# mkstepper23.net
KiCad netlist of a schematic drawn in EAGLE
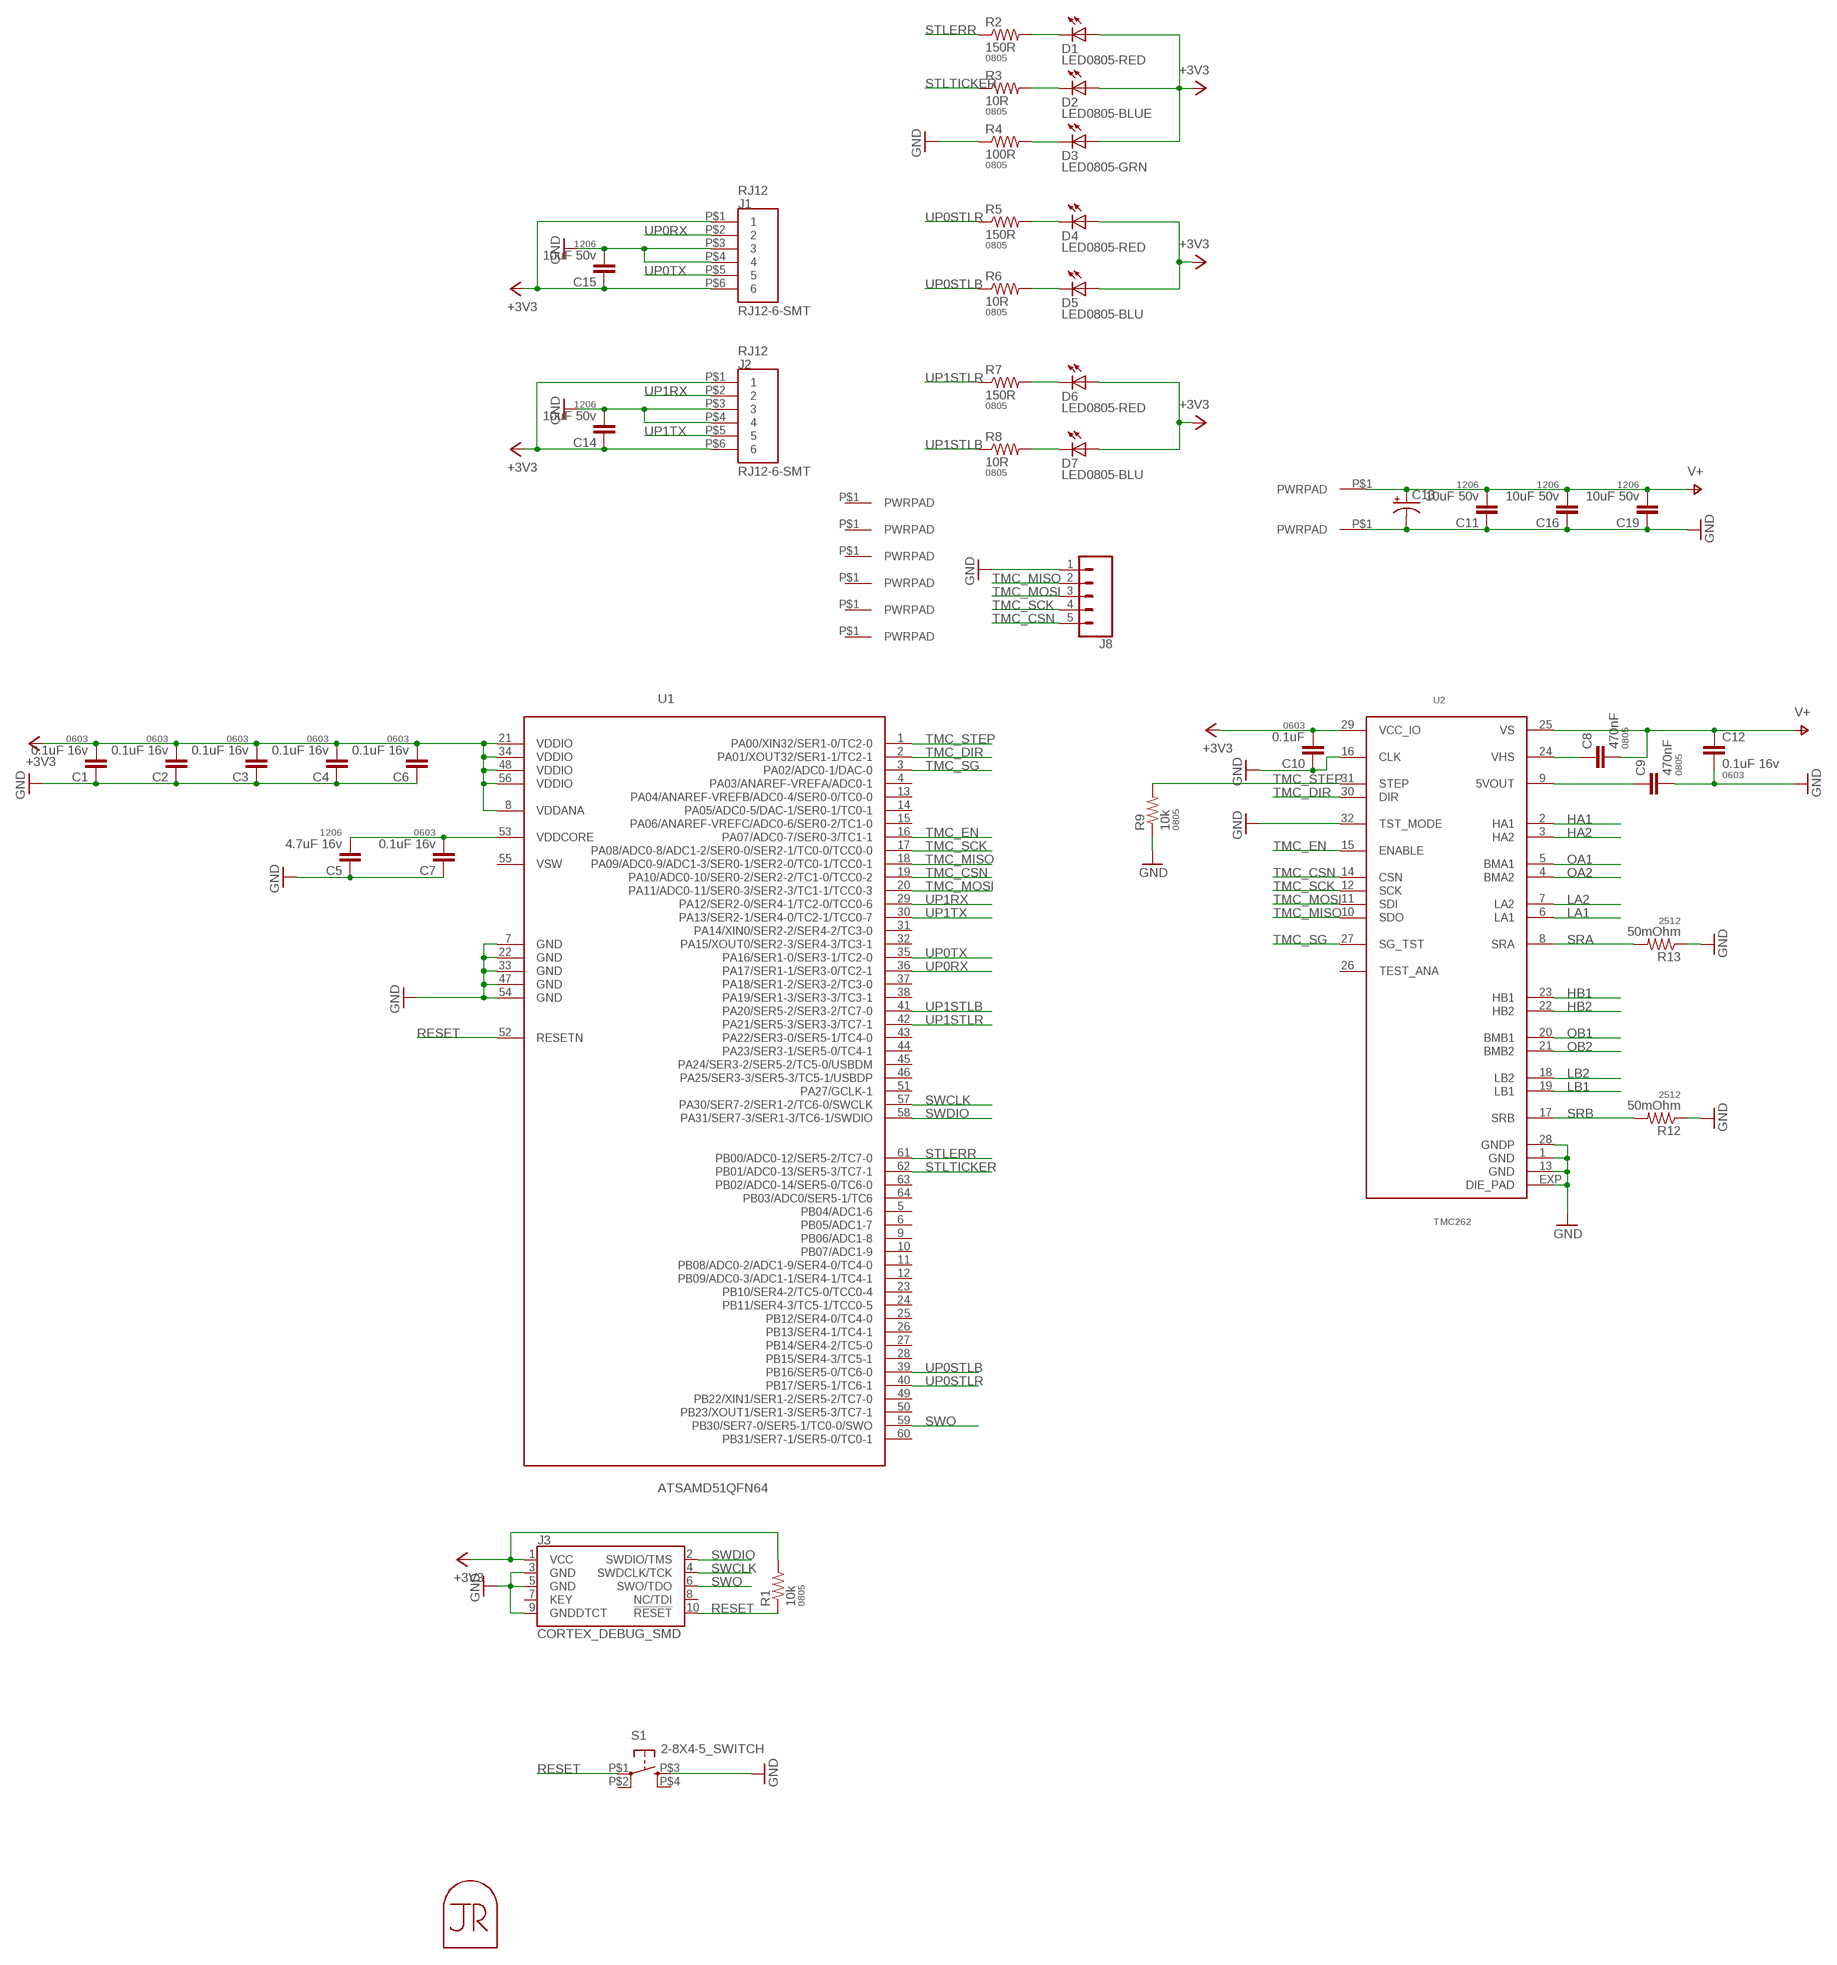
[diagram p0: schematic, sheet 1, part 1 of 2]
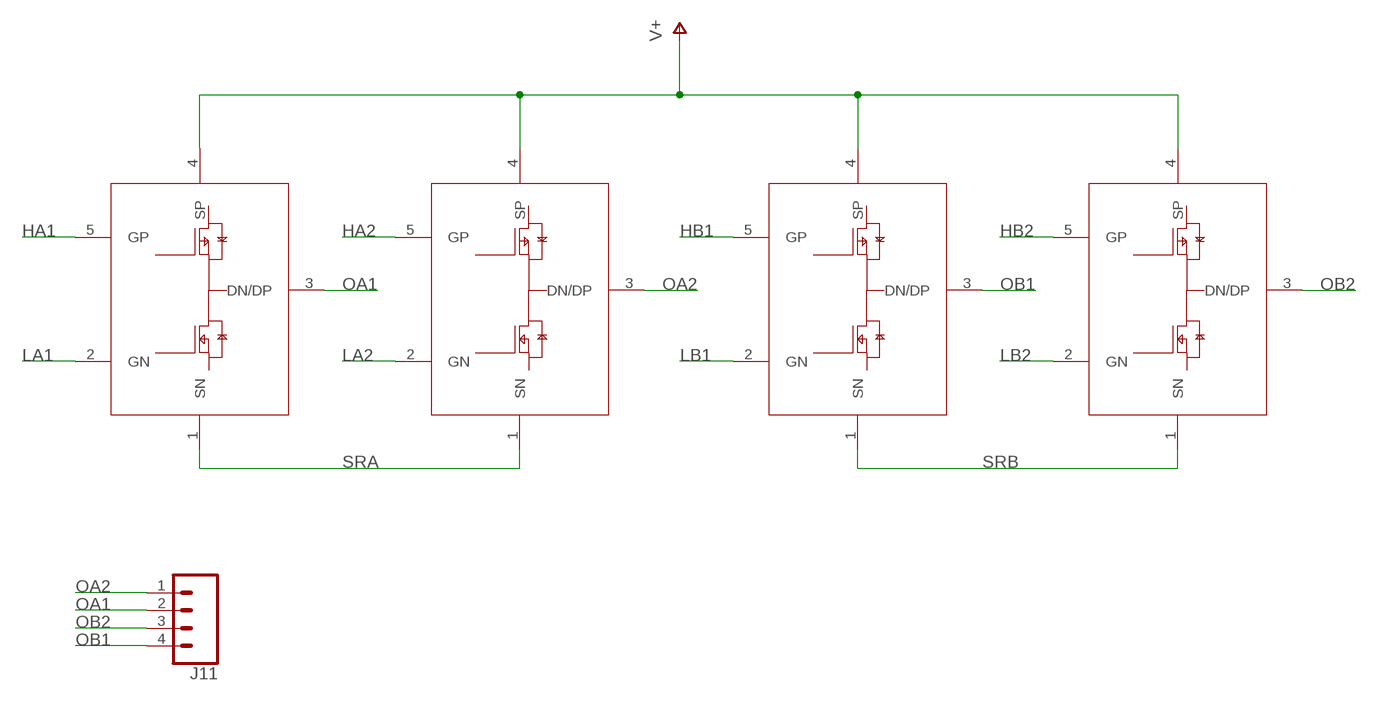
[diagram p1: schematic, sheet 1, part 2 of 2]

(export (version "E")
  (design (tool "Eeschema 10.0.6"))
  (components
    (comp (ref "C1")
      (value "0.1uF 16v")
      (footprint "eagle-import:0603-CAP")
      (libsource (lib "eagle-import") (part "CAP0603-CAP"))
    )
    (comp (ref "C2")
      (value "0.1uF 16v")
      (footprint "eagle-import:0603-CAP")
      (libsource (lib "eagle-import") (part "CAP0603-CAP"))
    )
    (comp (ref "C3")
      (value "0.1uF 16v")
      (footprint "eagle-import:0603-CAP")
      (libsource (lib "eagle-import") (part "CAP0603-CAP"))
    )
    (comp (ref "C4")
      (value "0.1uF 16v")
      (footprint "eagle-import:0603-CAP")
      (libsource (lib "eagle-import") (part "CAP0603-CAP"))
    )
    (comp (ref "C5")
      (value "4.7uF 16v")
      (footprint "eagle-import:1206")
      (libsource (lib "eagle-import") (part "CAP1206"))
    )
    (comp (ref "C6")
      (value "0.1uF 16v")
      (footprint "eagle-import:0603-CAP")
      (libsource (lib "eagle-import") (part "CAP0603-CAP"))
    )
    (comp (ref "C7")
      (value "0.1uF 16v")
      (footprint "eagle-import:0603-CAP")
      (libsource (lib "eagle-import") (part "CAP0603-CAP"))
    )
    (comp (ref "C8")
      (value "470nF")
      (footprint "eagle-import:0805")
      (libsource (lib "eagle-import") (part "CAP0805"))
    )
    (comp (ref "C9")
      (value "470nF")
      (footprint "eagle-import:0805")
      (libsource (lib "eagle-import") (part "CAP0805"))
    )
    (comp (ref "C10")
      (value "0.1uF")
      (footprint "eagle-import:0603-CAP")
      (libsource (lib "eagle-import") (part "CAP0603-CAP"))
    )
    (comp (ref "C11")
      (value "10uF 50v")
      (footprint "eagle-import:1206")
      (libsource (lib "eagle-import") (part "CAP1206"))
    )
    (comp (ref "C12")
      (value "0.1uF 16v")
      (footprint "eagle-import:0603-CAP")
      (libsource (lib "eagle-import") (part "CAP0603-CAP"))
    )
    (comp (ref "C13")
      (value "CAP-POL-6.6X6.6")
      (footprint "eagle-import:6.6X6.6-CAP")
      (libsource (lib "eagle-import") (part "CAP-POL-6.6X6.6"))
    )
    (comp (ref "C14")
      (value "10uF 50v")
      (footprint "eagle-import:1206")
      (libsource (lib "eagle-import") (part "CAP1206"))
    )
    (comp (ref "C15")
      (value "10uF 50v")
      (footprint "eagle-import:1206")
      (libsource (lib "eagle-import") (part "CAP1206"))
    )
    (comp (ref "C16")
      (value "10uF 50v")
      (footprint "eagle-import:1206")
      (libsource (lib "eagle-import") (part "CAP1206"))
    )
    (comp (ref "C19")
      (value "10uF 50v")
      (footprint "eagle-import:1206")
      (libsource (lib "eagle-import") (part "CAP1206"))
    )
    (comp (ref "D1")
      (value "LED0805-RED")
      (footprint "eagle-import:LED0805")
      (libsource (lib "eagle-import") (part "LED0805"))
    )
    (comp (ref "D2")
      (value "LED0805-BLUE")
      (footprint "eagle-import:LED0805")
      (libsource (lib "eagle-import") (part "LED0805"))
    )
    (comp (ref "D3")
      (value "LED0805-GRN")
      (footprint "eagle-import:LED0805")
      (libsource (lib "eagle-import") (part "LED0805"))
    )
    (comp (ref "D4")
      (value "LED0805-RED")
      (footprint "eagle-import:LED0805")
      (libsource (lib "eagle-import") (part "LED0805"))
    )
    (comp (ref "D5")
      (value "LED0805-BLU")
      (footprint "eagle-import:LED0805")
      (libsource (lib "eagle-import") (part "LED0805"))
    )
    (comp (ref "D6")
      (value "LED0805-RED")
      (footprint "eagle-import:LED0805")
      (libsource (lib "eagle-import") (part "LED0805"))
    )
    (comp (ref "D7")
      (value "LED0805-BLU")
      (footprint "eagle-import:LED0805")
      (libsource (lib "eagle-import") (part "LED0805"))
    )
    (comp (ref "J1")
      (value "RJ12-6-SMT")
      (footprint "eagle-import:RJ12-6-SMT")
      (libsource (lib "eagle-import") (part "RJ12-6-SMT"))
    )
    (comp (ref "J2")
      (value "RJ12-6-SMT")
      (footprint "eagle-import:RJ12-6-SMT")
      (libsource (lib "eagle-import") (part "RJ12-6-SMT"))
    )
    (comp (ref "J3")
      (value "CORTEX_DEBUG_SMD")
      (footprint "eagle-import:SAMTECH_FTSH-105-01")
      (libsource (lib "eagle-import") (part "CORTEX_DEBUG_SMD"))
    )
    (comp (ref "J4")
      (value "PWRPADM3-SKINNY")
      (footprint "eagle-import:PWRPAD_3-25MM-SKINNY")
      (libsource (lib "eagle-import") (part "PWRPADM3-SKINNY"))
    )
    (comp (ref "J5")
      (value "PWRPADM3-SKINNY")
      (footprint "eagle-import:PWRPAD_3-25MM-SKINNY")
      (libsource (lib "eagle-import") (part "PWRPADM3-SKINNY"))
    )
    (comp (ref "J6")
      (value "PWRPADM3-SKINNY")
      (footprint "eagle-import:PWRPAD_3-25MM-SKINNY")
      (libsource (lib "eagle-import") (part "PWRPADM3-SKINNY"))
    )
    (comp (ref "J7")
      (value "PWRPADM3-SKINNY")
      (footprint "eagle-import:PWRPAD_3-25MM-SKINNY")
      (libsource (lib "eagle-import") (part "PWRPADM3-SKINNY"))
    )
    (comp (ref "J8")
      (value "CONN_05NO_SILK")
      (footprint "eagle-import:1X05_NO_SILK")
      (libsource (lib "eagle-import") (part "CONN_05NO_SILK"))
    )
    (comp (ref "J9")
      (value "PWRPAD")
      (footprint "eagle-import:PWRPAD_M3-PEM-MOUNT")
      (libsource (lib "eagle-import") (part "PWRPAD"))
    )
    (comp (ref "J10")
      (value "PWRPAD")
      (footprint "eagle-import:PWRPAD_M3-PEM-MOUNT")
      (libsource (lib "eagle-import") (part "PWRPAD"))
    )
    (comp (ref "J11")
      (value "CONN_04LONGPADS")
      (footprint "eagle-import:1X04_LONGPADS")
      (libsource (lib "eagle-import") (part "CONN_04LONGPADS"))
    )
    (comp (ref "J12")
      (value "PWRPADM3-SKINNY")
      (footprint "eagle-import:PWRPAD_3-25MM-SKINNY")
      (libsource (lib "eagle-import") (part "PWRPADM3-SKINNY"))
    )
    (comp (ref "J13")
      (value "PWRPADM3-SKINNY")
      (footprint "eagle-import:PWRPAD_3-25MM-SKINNY")
      (libsource (lib "eagle-import") (part "PWRPADM3-SKINNY"))
    )
    (comp (ref "MP1")
      (value "JRTOMBSTONE")
      (footprint "eagle-import:JRTOMBSTONE")
      (libsource (lib "eagle-import") (part "JRTOMBSTONE"))
    )
    (comp (ref "Q1")
      (value "PNPAIR-FDD8424H")
      (footprint "eagle-import:DPAK-5")
      (libsource (lib "eagle-import") (part "PNPAIR-FDD8424H"))
    )
    (comp (ref "Q2")
      (value "PNPAIR-FDD8424H")
      (footprint "eagle-import:DPAK-5")
      (libsource (lib "eagle-import") (part "PNPAIR-FDD8424H"))
    )
    (comp (ref "Q3")
      (value "PNPAIR-FDD8424H")
      (footprint "eagle-import:DPAK-5")
      (libsource (lib "eagle-import") (part "PNPAIR-FDD8424H"))
    )
    (comp (ref "Q4")
      (value "PNPAIR-FDD8424H")
      (footprint "eagle-import:DPAK-5")
      (libsource (lib "eagle-import") (part "PNPAIR-FDD8424H"))
    )
    (comp (ref "R1")
      (value "10k")
      (footprint "eagle-import:0805")
      (libsource (lib "eagle-import") (part "RESISTOR0805-RES"))
    )
    (comp (ref "R2")
      (value "150R")
      (footprint "eagle-import:0805")
      (libsource (lib "eagle-import") (part "RESISTOR0805-RES"))
    )
    (comp (ref "R3")
      (value "10R")
      (footprint "eagle-import:0805")
      (libsource (lib "eagle-import") (part "RESISTOR0805-RES"))
    )
    (comp (ref "R4")
      (value "100R")
      (footprint "eagle-import:0805")
      (libsource (lib "eagle-import") (part "RESISTOR0805-RES"))
    )
    (comp (ref "R5")
      (value "150R")
      (footprint "eagle-import:0805")
      (libsource (lib "eagle-import") (part "RESISTOR0805-RES"))
    )
    (comp (ref "R6")
      (value "10R")
      (footprint "eagle-import:0805")
      (libsource (lib "eagle-import") (part "RESISTOR0805-RES"))
    )
    (comp (ref "R7")
      (value "150R")
      (footprint "eagle-import:0805")
      (libsource (lib "eagle-import") (part "RESISTOR0805-RES"))
    )
    (comp (ref "R8")
      (value "10R")
      (footprint "eagle-import:0805")
      (libsource (lib "eagle-import") (part "RESISTOR0805-RES"))
    )
    (comp (ref "R9")
      (value "10k")
      (footprint "eagle-import:0805")
      (libsource (lib "eagle-import") (part "RESISTOR0805-RES"))
    )
    (comp (ref "R12")
      (value "50mOhm")
      (footprint "eagle-import:R2512")
      (libsource (lib "eagle-import") (part "RESISTOR2512"))
    )
    (comp (ref "R13")
      (value "50mOhm")
      (footprint "eagle-import:R2512")
      (libsource (lib "eagle-import") (part "RESISTOR2512"))
    )
    (comp (ref "S1")
      (value "2-8X4-5_SWITCH")
      (footprint "eagle-import:TACT-SWITCH-KMR6")
      (libsource (lib "eagle-import") (part "2-8X4-5_SWITCH"))
    )
    (comp (ref "U1")
      (value "ATSAMD51QFN64")
      (footprint "eagle-import:QFN-64-9X9MM")
      (libsource (lib "eagle-import") (part "ATSAMD51QFN64"))
    )
    (comp (ref "U2")
      (value "TMC262")
      (footprint "eagle-import:QFN32")
      (libsource (lib "eagle-import") (part "TMC262"))
    )
  )
  (nets
    (net (code "1") (name "+3V3") (class "Default")
      (node (ref "C1") (pin "2") (pinfunction "2_2") (pintype "passive"))
      (node (ref "C10") (pin "2") (pinfunction "2_2") (pintype "passive"))
      (node (ref "C14") (pin "1") (pinfunction "1_1") (pintype "passive"))
      (node (ref "C15") (pin "1") (pinfunction "1_1") (pintype "passive"))
      (node (ref "C2") (pin "2") (pinfunction "2_2") (pintype "passive"))
      (node (ref "C3") (pin "2") (pinfunction "2_2") (pintype "passive"))
      (node (ref "C4") (pin "2") (pinfunction "2_2") (pintype "passive"))
      (node (ref "C6") (pin "2") (pinfunction "2_2") (pintype "passive"))
      (node (ref "D1") (pin "1") (pinfunction "A_1") (pintype "passive"))
      (node (ref "D2") (pin "1") (pinfunction "A_1") (pintype "passive"))
      (node (ref "D3") (pin "1") (pinfunction "A_1") (pintype "passive"))
      (node (ref "D4") (pin "1") (pinfunction "A_1") (pintype "passive"))
      (node (ref "D5") (pin "1") (pinfunction "A_1") (pintype "passive"))
      (node (ref "D6") (pin "1") (pinfunction "A_1") (pintype "passive"))
      (node (ref "D7") (pin "1") (pinfunction "A_1") (pintype "passive"))
      (node (ref "J1") (pin "P$1") (pinfunction "1_P$1") (pintype "bidirectional"))
      (node (ref "J1") (pin "P$6") (pinfunction "6_P$6") (pintype "bidirectional"))
      (node (ref "J2") (pin "P$1") (pinfunction "1_P$1") (pintype "bidirectional"))
      (node (ref "J2") (pin "P$6") (pinfunction "6_P$6") (pintype "bidirectional"))
      (node (ref "J3") (pin "1") (pinfunction "VCC_1") (pintype "bidirectional"))
      (node (ref "R1") (pin "2") (pinfunction "2_2") (pintype "passive"))
      (node (ref "U1") (pin "21") (pinfunction "VDDIO_21") (pintype "bidirectional"))
      (node (ref "U1") (pin "34") (pinfunction "VDDIO_34") (pintype "bidirectional"))
      (node (ref "U1") (pin "48") (pinfunction "VDDIO_48") (pintype "bidirectional"))
      (node (ref "U1") (pin "56") (pinfunction "VDDIO_56") (pintype "bidirectional"))
      (node (ref "U1") (pin "8") (pinfunction "VDDANA_8") (pintype "bidirectional"))
      (node (ref "U2") (pin "29") (pinfunction "VCC_IO_29") (pintype "bidirectional"))
    )
    (net (code "2") (name "/HA1") (class "Default")
      (node (ref "Q1") (pin "5") (pinfunction "GP_5") (pintype "bidirectional"))
      (node (ref "U2") (pin "2") (pinfunction "HA1_2") (pintype "bidirectional"))
    )
    (net (code "3") (name "/HA2") (class "Default")
      (node (ref "Q2") (pin "5") (pinfunction "GP_5") (pintype "bidirectional"))
      (node (ref "U2") (pin "3") (pinfunction "HA2_3") (pintype "bidirectional"))
    )
    (net (code "4") (name "/HB1") (class "Default")
      (node (ref "Q3") (pin "5") (pinfunction "GP_5") (pintype "bidirectional"))
      (node (ref "U2") (pin "23") (pinfunction "HB1_23") (pintype "bidirectional"))
    )
    (net (code "5") (name "/HB2") (class "Default")
      (node (ref "Q4") (pin "5") (pinfunction "GP_5") (pintype "bidirectional"))
      (node (ref "U2") (pin "22") (pinfunction "HB2_22") (pintype "bidirectional"))
    )
    (net (code "6") (name "/LA1") (class "Default")
      (node (ref "Q1") (pin "2") (pinfunction "GN_2") (pintype "bidirectional"))
      (node (ref "U2") (pin "6") (pinfunction "LA1_6") (pintype "bidirectional"))
    )
    (net (code "7") (name "/LA2") (class "Default")
      (node (ref "Q2") (pin "2") (pinfunction "GN_2") (pintype "bidirectional"))
      (node (ref "U2") (pin "7") (pinfunction "LA2_7") (pintype "bidirectional"))
    )
    (net (code "8") (name "/LB1") (class "Default")
      (node (ref "Q3") (pin "2") (pinfunction "GN_2") (pintype "bidirectional"))
      (node (ref "U2") (pin "19") (pinfunction "LB1_19") (pintype "bidirectional"))
    )
    (net (code "9") (name "/LB2") (class "Default")
      (node (ref "Q4") (pin "2") (pinfunction "GN_2") (pintype "bidirectional"))
      (node (ref "U2") (pin "18") (pinfunction "LB2_18") (pintype "bidirectional"))
    )
    (net (code "10") (name "/OA1") (class "Default")
      (node (ref "J11") (pin "2") (pinfunction "2_2") (pintype "passive"))
      (node (ref "Q1") (pin "3") (pinfunction "DN/DP_3") (pintype "bidirectional"))
      (node (ref "U2") (pin "5") (pinfunction "BMA1_5") (pintype "bidirectional"))
    )
    (net (code "11") (name "/OA2") (class "Default")
      (node (ref "J11") (pin "1") (pinfunction "1_1") (pintype "passive"))
      (node (ref "Q2") (pin "3") (pinfunction "DN/DP_3") (pintype "bidirectional"))
      (node (ref "U2") (pin "4") (pinfunction "BMA2_4") (pintype "bidirectional"))
    )
    (net (code "12") (name "/OB1") (class "Default")
      (node (ref "J11") (pin "4") (pinfunction "4_4") (pintype "passive"))
      (node (ref "Q3") (pin "3") (pinfunction "DN/DP_3") (pintype "bidirectional"))
      (node (ref "U2") (pin "20") (pinfunction "BMB1_20") (pintype "bidirectional"))
    )
    (net (code "13") (name "/OB2") (class "Default")
      (node (ref "J11") (pin "3") (pinfunction "3_3") (pintype "passive"))
      (node (ref "Q4") (pin "3") (pinfunction "DN/DP_3") (pintype "bidirectional"))
      (node (ref "U2") (pin "21") (pinfunction "BMB2_21") (pintype "bidirectional"))
    )
    (net (code "14") (name "/RESET") (class "Default")
      (node (ref "J3") (pin "10") (pinfunction "~{RESET}_10") (pintype "bidirectional"))
      (node (ref "R1") (pin "1") (pinfunction "1_1") (pintype "passive"))
      (node (ref "S1") (pin "P$1") (pinfunction "P_P$1") (pintype "passive"))
      (node (ref "U1") (pin "52") (pinfunction "RESETN_52") (pintype "bidirectional"))
    )
    (net (code "15") (name "/SRA") (class "Default")
      (node (ref "Q1") (pin "1") (pinfunction "SN_1") (pintype "bidirectional"))
      (node (ref "Q2") (pin "1") (pinfunction "SN_1") (pintype "bidirectional"))
      (node (ref "R13") (pin "2") (pinfunction "2_2") (pintype "passive"))
      (node (ref "U2") (pin "8") (pinfunction "SRA_8") (pintype "bidirectional"))
    )
    (net (code "16") (name "/SRB") (class "Default")
      (node (ref "Q3") (pin "1") (pinfunction "SN_1") (pintype "bidirectional"))
      (node (ref "Q4") (pin "1") (pinfunction "SN_1") (pintype "bidirectional"))
      (node (ref "R12") (pin "2") (pinfunction "2_2") (pintype "passive"))
      (node (ref "U2") (pin "17") (pinfunction "SRB_17") (pintype "bidirectional"))
    )
    (net (code "17") (name "/STLERR") (class "Default")
      (node (ref "R2") (pin "1") (pinfunction "1_1") (pintype "passive"))
      (node (ref "U1") (pin "61") (pinfunction "PB00/ADC0-12/SER5-2/TC7-0_61") (pintype "bidirectional"))
    )
    (net (code "18") (name "/STLTICKER") (class "Default")
      (node (ref "R3") (pin "1") (pinfunction "1_1") (pintype "passive"))
      (node (ref "U1") (pin "62") (pinfunction "PB01/ADC0-13/SER5-3/TC7-1_62") (pintype "bidirectional"))
    )
    (net (code "19") (name "/SWCLK") (class "Default")
      (node (ref "J3") (pin "4") (pinfunction "SWDCLK/TCK_4") (pintype "bidirectional"))
      (node (ref "U1") (pin "57") (pinfunction "PA30/SER7-2/SER1-2/TC6-0/SWCLK_57") (pintype "bidirectional"))
    )
    (net (code "20") (name "/SWDIO") (class "Default")
      (node (ref "J3") (pin "2") (pinfunction "SWDIO/TMS_2") (pintype "bidirectional"))
      (node (ref "U1") (pin "58") (pinfunction "PA31/SER7-3/SER1-3/TC6-1/SWDIO_58") (pintype "bidirectional"))
    )
    (net (code "21") (name "/SWO") (class "Default")
      (node (ref "J3") (pin "6") (pinfunction "SWO/TDO_6") (pintype "bidirectional"))
      (node (ref "U1") (pin "59") (pinfunction "PB30/SER7-0/SER5-1/TC0-0/SWO_59") (pintype "bidirectional"))
    )
    (net (code "22") (name "/TMC_CSN") (class "Default")
      (node (ref "J8") (pin "5") (pinfunction "5_5") (pintype "passive"))
      (node (ref "U1") (pin "19") (pinfunction "PA10/ADC0-10/SER0-2/SER2-2/TC1-0/TCC0-2_19") (pintype "bidirectional"))
      (node (ref "U2") (pin "14") (pinfunction "CSN_14") (pintype "bidirectional"))
    )
    (net (code "23") (name "/TMC_DIR") (class "Default")
      (node (ref "U1") (pin "2") (pinfunction "PA01/XOUT32/SER1-1/TC2-1_2") (pintype "bidirectional"))
      (node (ref "U2") (pin "30") (pinfunction "DIR_30") (pintype "bidirectional"))
    )
    (net (code "24") (name "/TMC_EN") (class "Default")
      (node (ref "U1") (pin "16") (pinfunction "PA07/ADC0-7/SER0-3/TC1-1_16") (pintype "bidirectional"))
      (node (ref "U2") (pin "15") (pinfunction "ENABLE_15") (pintype "bidirectional"))
    )
    (net (code "25") (name "/TMC_MISO") (class "Default")
      (node (ref "J8") (pin "2") (pinfunction "2_2") (pintype "passive"))
      (node (ref "U1") (pin "18") (pinfunction "PA09/ADC0-9/ADC1-3/SER0-1/SER2-0/TC0-1/TCC0-1_18") (pintype "bidirectional"))
      (node (ref "U2") (pin "10") (pinfunction "SDO_10") (pintype "bidirectional"))
    )
    (net (code "26") (name "/TMC_MOSI") (class "Default")
      (node (ref "J8") (pin "3") (pinfunction "3_3") (pintype "passive"))
      (node (ref "U1") (pin "20") (pinfunction "PA11/ADC0-11/SER0-3/SER2-3/TC1-1/TCC0-3_20") (pintype "bidirectional"))
      (node (ref "U2") (pin "11") (pinfunction "SDI_11") (pintype "bidirectional"))
    )
    (net (code "27") (name "/TMC_SCK") (class "Default")
      (node (ref "J8") (pin "4") (pinfunction "4_4") (pintype "passive"))
      (node (ref "U1") (pin "17") (pinfunction "PA08/ADC0-8/ADC1-2/SER0-0/SER2-1/TC0-0/TCC0-0_17") (pintype "bidirectional"))
      (node (ref "U2") (pin "12") (pinfunction "SCK_12") (pintype "bidirectional"))
    )
    (net (code "28") (name "/TMC_SG") (class "Default")
      (node (ref "U1") (pin "3") (pinfunction "PA02/ADC0-1/DAC-0_3") (pintype "bidirectional"))
      (node (ref "U2") (pin "27") (pinfunction "SG_TST_27") (pintype "bidirectional"))
    )
    (net (code "29") (name "/TMC_STEP") (class "Default")
      (node (ref "R9") (pin "2") (pinfunction "2_2") (pintype "passive"))
      (node (ref "U1") (pin "1") (pinfunction "PA00/XIN32/SER1-0/TC2-0_1") (pintype "bidirectional"))
      (node (ref "U2") (pin "31") (pinfunction "STEP_31") (pintype "bidirectional"))
    )
    (net (code "30") (name "/UP0RX") (class "Default")
      (node (ref "J1") (pin "P$2") (pinfunction "2_P$2") (pintype "bidirectional"))
      (node (ref "U1") (pin "36") (pinfunction "PA17/SER1-1/SER3-0/TC2-1_36") (pintype "bidirectional"))
    )
    (net (code "31") (name "/UP0STLB") (class "Default")
      (node (ref "R6") (pin "1") (pinfunction "1_1") (pintype "passive"))
      (node (ref "U1") (pin "39") (pinfunction "PB16/SER5-0/TC6-0_39") (pintype "bidirectional"))
    )
    (net (code "32") (name "/UP0STLR") (class "Default")
      (node (ref "R5") (pin "1") (pinfunction "1_1") (pintype "passive"))
      (node (ref "U1") (pin "40") (pinfunction "PB17/SER5-1/TC6-1_40") (pintype "bidirectional"))
    )
    (net (code "33") (name "/UP0TX") (class "Default")
      (node (ref "J1") (pin "P$5") (pinfunction "5_P$5") (pintype "bidirectional"))
      (node (ref "U1") (pin "35") (pinfunction "PA16/SER1-0/SER3-1/TC2-0_35") (pintype "bidirectional"))
    )
    (net (code "34") (name "/UP1RX") (class "Default")
      (node (ref "J2") (pin "P$2") (pinfunction "2_P$2") (pintype "bidirectional"))
      (node (ref "U1") (pin "29") (pinfunction "PA12/SER2-0/SER4-1/TC2-0/TCC0-6_29") (pintype "bidirectional"))
    )
    (net (code "35") (name "/UP1STLB") (class "Default")
      (node (ref "R8") (pin "1") (pinfunction "1_1") (pintype "passive"))
      (node (ref "U1") (pin "41") (pinfunction "PA20/SER5-2/SER3-2/TC7-0_41") (pintype "bidirectional"))
    )
    (net (code "36") (name "/UP1STLR") (class "Default")
      (node (ref "R7") (pin "1") (pinfunction "1_1") (pintype "passive"))
      (node (ref "U1") (pin "42") (pinfunction "PA21/SER5-3/SER3-3/TC7-1_42") (pintype "bidirectional"))
    )
    (net (code "37") (name "/UP1TX") (class "Default")
      (node (ref "J2") (pin "P$5") (pinfunction "5_P$5") (pintype "bidirectional"))
      (node (ref "U1") (pin "30") (pinfunction "PA13/SER2-1/SER4-0/TC2-1/TCC0-7_30") (pintype "bidirectional"))
    )
    (net (code "38") (name "GND") (class "Default")
      (node (ref "C1") (pin "1") (pinfunction "1_1") (pintype "passive"))
      (node (ref "C10") (pin "1") (pinfunction "1_1") (pintype "passive"))
      (node (ref "C11") (pin "1") (pinfunction "1_1") (pintype "passive"))
      (node (ref "C12") (pin "2") (pinfunction "2_2") (pintype "passive"))
      (node (ref "C13") (pin "-") (pinfunction "-_-") (pintype "passive"))
      (node (ref "C14") (pin "2") (pinfunction "2_2") (pintype "passive"))
      (node (ref "C15") (pin "2") (pinfunction "2_2") (pintype "passive"))
      (node (ref "C16") (pin "1") (pinfunction "1_1") (pintype "passive"))
      (node (ref "C19") (pin "1") (pinfunction "1_1") (pintype "passive"))
      (node (ref "C2") (pin "1") (pinfunction "1_1") (pintype "passive"))
      (node (ref "C3") (pin "1") (pinfunction "1_1") (pintype "passive"))
      (node (ref "C4") (pin "1") (pinfunction "1_1") (pintype "passive"))
      (node (ref "C5") (pin "1") (pinfunction "1_1") (pintype "passive"))
      (node (ref "C6") (pin "1") (pinfunction "1_1") (pintype "passive"))
      (node (ref "C7") (pin "1") (pinfunction "1_1") (pintype "passive"))
      (node (ref "C9") (pin "2") (pinfunction "2_2") (pintype "passive"))
      (node (ref "J1") (pin "P$3") (pinfunction "3_P$3") (pintype "bidirectional"))
      (node (ref "J1") (pin "P$4") (pinfunction "4_P$4") (pintype "bidirectional"))
      (node (ref "J10") (pin "P$1") (pinfunction "PWRPAD_P$1") (pintype "bidirectional"))
      (node (ref "J2") (pin "P$3") (pinfunction "3_P$3") (pintype "bidirectional"))
      (node (ref "J2") (pin "P$4") (pinfunction "4_P$4") (pintype "bidirectional"))
      (node (ref "J3") (pin "3") (pinfunction "GND_3") (pintype "bidirectional"))
      (node (ref "J3") (pin "5") (pinfunction "GND_5") (pintype "bidirectional"))
      (node (ref "J3") (pin "9") (pinfunction "GNDDTCT_9") (pintype "bidirectional"))
      (node (ref "J8") (pin "1") (pinfunction "1_1") (pintype "passive"))
      (node (ref "R12") (pin "1") (pinfunction "1_1") (pintype "passive"))
      (node (ref "R13") (pin "1") (pinfunction "1_1") (pintype "passive"))
      (node (ref "R4") (pin "1") (pinfunction "1_1") (pintype "passive"))
      (node (ref "R9") (pin "1") (pinfunction "1_1") (pintype "passive"))
      (node (ref "S1") (pin "P$3") (pinfunction "S_P$3") (pintype "passive"))
      (node (ref "U1") (pin "22") (pinfunction "GND_22") (pintype "bidirectional"))
      (node (ref "U1") (pin "33") (pinfunction "GND_33") (pintype "bidirectional"))
      (node (ref "U1") (pin "47") (pinfunction "GND_47") (pintype "bidirectional"))
      (node (ref "U1") (pin "54") (pinfunction "GND_54") (pintype "bidirectional"))
      (node (ref "U1") (pin "7") (pinfunction "GND_7") (pintype "bidirectional"))
      (node (ref "U2") (pin "1") (pinfunction "GND_1") (pintype "bidirectional"))
      (node (ref "U2") (pin "13") (pinfunction "GND_13") (pintype "bidirectional"))
      (node (ref "U2") (pin "16") (pinfunction "CLK_16") (pintype "bidirectional"))
      (node (ref "U2") (pin "28") (pinfunction "GNDP_28") (pintype "bidirectional"))
      (node (ref "U2") (pin "32") (pinfunction "TST_MODE_32") (pintype "bidirectional"))
      (node (ref "U2") (pin "EXP") (pinfunction "DIE_PAD_EXP") (pintype "bidirectional"))
    )
    (net (code "39") (name "Net-(D1-C)") (class "Default")
      (node (ref "D1") (pin "2") (pinfunction "C_2") (pintype "passive"))
      (node (ref "R2") (pin "2") (pinfunction "2_2") (pintype "passive"))
    )
    (net (code "40") (name "Net-(D2-C)") (class "Default")
      (node (ref "D2") (pin "2") (pinfunction "C_2") (pintype "passive"))
      (node (ref "R3") (pin "2") (pinfunction "2_2") (pintype "passive"))
    )
    (net (code "41") (name "Net-(D3-C)") (class "Default")
      (node (ref "D3") (pin "2") (pinfunction "C_2") (pintype "passive"))
      (node (ref "R4") (pin "2") (pinfunction "2_2") (pintype "passive"))
    )
    (net (code "42") (name "Net-(D4-C)") (class "Default")
      (node (ref "D4") (pin "2") (pinfunction "C_2") (pintype "passive"))
      (node (ref "R5") (pin "2") (pinfunction "2_2") (pintype "passive"))
    )
    (net (code "43") (name "Net-(D5-C)") (class "Default")
      (node (ref "D5") (pin "2") (pinfunction "C_2") (pintype "passive"))
      (node (ref "R6") (pin "2") (pinfunction "2_2") (pintype "passive"))
    )
    (net (code "44") (name "Net-(D6-C)") (class "Default")
      (node (ref "D6") (pin "2") (pinfunction "C_2") (pintype "passive"))
      (node (ref "R7") (pin "2") (pinfunction "2_2") (pintype "passive"))
    )
    (net (code "45") (name "Net-(D7-C)") (class "Default")
      (node (ref "D7") (pin "2") (pinfunction "C_2") (pintype "passive"))
      (node (ref "R8") (pin "2") (pinfunction "2_2") (pintype "passive"))
    )
    (net (code "46") (name "Net-(U1-VDDCORE)") (class "Default")
      (node (ref "C5") (pin "2") (pinfunction "2_2") (pintype "passive"))
      (node (ref "C7") (pin "2") (pinfunction "2_2") (pintype "passive"))
      (node (ref "U1") (pin "53") (pinfunction "VDDCORE_53") (pintype "bidirectional"))
    )
    (net (code "47") (name "Net-(U2-5VOUT)") (class "Default")
      (node (ref "C9") (pin "1") (pinfunction "1_1") (pintype "passive"))
      (node (ref "U2") (pin "9") (pinfunction "5VOUT_9") (pintype "bidirectional"))
    )
    (net (code "48") (name "Net-(U2-VHS)") (class "Default")
      (node (ref "C8") (pin "1") (pinfunction "1_1") (pintype "passive"))
      (node (ref "U2") (pin "24") (pinfunction "VHS_24") (pintype "bidirectional"))
    )
    (net (code "49") (name "V+") (class "Default")
      (node (ref "C11") (pin "2") (pinfunction "2_2") (pintype "passive"))
      (node (ref "C12") (pin "1") (pinfunction "1_1") (pintype "passive"))
      (node (ref "C13") (pin "+") (pinfunction "+_+") (pintype "passive"))
      (node (ref "C16") (pin "2") (pinfunction "2_2") (pintype "passive"))
      (node (ref "C19") (pin "2") (pinfunction "2_2") (pintype "passive"))
      (node (ref "C8") (pin "2") (pinfunction "2_2") (pintype "passive"))
      (node (ref "J9") (pin "P$1") (pinfunction "PWRPAD_P$1") (pintype "bidirectional"))
      (node (ref "Q1") (pin "4") (pinfunction "SP_4") (pintype "bidirectional"))
      (node (ref "Q2") (pin "4") (pinfunction "SP_4") (pintype "bidirectional"))
      (node (ref "Q3") (pin "4") (pinfunction "SP_4") (pintype "bidirectional"))
      (node (ref "Q4") (pin "4") (pinfunction "SP_4") (pintype "bidirectional"))
      (node (ref "U2") (pin "25") (pinfunction "VS_25") (pintype "bidirectional"))
    )
    (net (code "50") (name "unconnected-(J3-KEY-Pad7)") (class "Default")
      (node (ref "J3") (pin "7") (pinfunction "KEY_7") (pintype "bidirectional"))
    )
    (net (code "51") (name "unconnected-(J3-NC{slash}TDI-Pad8)") (class "Default")
      (node (ref "J3") (pin "8") (pinfunction "NC/TDI_8") (pintype "bidirectional"))
    )
    (net (code "52") (name "unconnected-(J4-PWRPAD-PadP$1)") (class "Default")
      (node (ref "J4") (pin "P$1") (pinfunction "PWRPAD_P$1") (pintype "bidirectional"))
    )
    (net (code "53") (name "unconnected-(J5-PWRPAD-PadP$1)") (class "Default")
      (node (ref "J5") (pin "P$1") (pinfunction "PWRPAD_P$1") (pintype "bidirectional"))
    )
    (net (code "54") (name "unconnected-(J6-PWRPAD-PadP$1)") (class "Default")
      (node (ref "J6") (pin "P$1") (pinfunction "PWRPAD_P$1") (pintype "bidirectional"))
    )
    (net (code "55") (name "unconnected-(J7-PWRPAD-PadP$1)") (class "Default")
      (node (ref "J7") (pin "P$1") (pinfunction "PWRPAD_P$1") (pintype "bidirectional"))
    )
    (net (code "56") (name "unconnected-(J12-PWRPAD-PadP$1)") (class "Default")
      (node (ref "J12") (pin "P$1") (pinfunction "PWRPAD_P$1") (pintype "bidirectional"))
    )
    (net (code "57") (name "unconnected-(J13-PWRPAD-PadP$1)") (class "Default")
      (node (ref "J13") (pin "P$1") (pinfunction "PWRPAD_P$1") (pintype "bidirectional"))
    )
    (net (code "58") (name "unconnected-(S1-P1-PadP$2)") (class "Default")
      (node (ref "S1") (pin "P$2") (pinfunction "P1_P$2") (pintype "passive"))
    )
    (net (code "59") (name "unconnected-(S1-S1-PadP$4)") (class "Default")
      (node (ref "S1") (pin "P$4") (pinfunction "S1_P$4") (pintype "passive"))
    )
    (net (code "60") (name "unconnected-(U1-PA03{slash}ANAREF-VREFA{slash}ADC0-1-Pad4)") (class "Default")
      (node (ref "U1") (pin "4") (pinfunction "PA03/ANAREF-VREFA/ADC0-1_4") (pintype "bidirectional"))
    )
    (net (code "61") (name "unconnected-(U1-PA04{slash}ANAREF-VREFB{slash}ADC0-4{slash}SER0-0{slash}TC0-0-Pad13)") (class "Default")
      (node (ref "U1") (pin "13") (pinfunction "PA04/ANAREF-VREFB/ADC0-4/SER0-0/TC0-0_13") (pintype "bidirectional"))
    )
    (net (code "62") (name "unconnected-(U1-PA05{slash}ADC0-5{slash}DAC-1{slash}SER0-1{slash}TC0-1-Pad14)") (class "Default")
      (node (ref "U1") (pin "14") (pinfunction "PA05/ADC0-5/DAC-1/SER0-1/TC0-1_14") (pintype "bidirectional"))
    )
    (net (code "63") (name "unconnected-(U1-PA06{slash}ANAREF-VREFC{slash}ADC0-6{slash}SER0-2{slash}TC1-0-Pad15)") (class "Default")
      (node (ref "U1") (pin "15") (pinfunction "PA06/ANAREF-VREFC/ADC0-6/SER0-2/TC1-0_15") (pintype "bidirectional"))
    )
    (net (code "64") (name "unconnected-(U1-PA14{slash}XIN0{slash}SER2-2{slash}SER4-2{slash}TC3-0-Pad31)") (class "Default")
      (node (ref "U1") (pin "31") (pinfunction "PA14/XIN0/SER2-2/SER4-2/TC3-0_31") (pintype "bidirectional"))
    )
    (net (code "65") (name "unconnected-(U1-PA15{slash}XOUT0{slash}SER2-3{slash}SER4-3{slash}TC3-1-Pad32)") (class "Default")
      (node (ref "U1") (pin "32") (pinfunction "PA15/XOUT0/SER2-3/SER4-3/TC3-1_32") (pintype "bidirectional"))
    )
    (net (code "66") (name "unconnected-(U1-PA18{slash}SER1-2{slash}SER3-2{slash}TC3-0-Pad37)") (class "Default")
      (node (ref "U1") (pin "37") (pinfunction "PA18/SER1-2/SER3-2/TC3-0_37") (pintype "bidirectional"))
    )
    (net (code "67") (name "unconnected-(U1-PA19{slash}SER1-3{slash}SER3-3{slash}TC3-1-Pad38)") (class "Default")
      (node (ref "U1") (pin "38") (pinfunction "PA19/SER1-3/SER3-3/TC3-1_38") (pintype "bidirectional"))
    )
    (net (code "68") (name "unconnected-(U1-PA22{slash}SER3-0{slash}SER5-1{slash}TC4-0-Pad43)") (class "Default")
      (node (ref "U1") (pin "43") (pinfunction "PA22/SER3-0/SER5-1/TC4-0_43") (pintype "bidirectional"))
    )
    (net (code "69") (name "unconnected-(U1-PA23{slash}SER3-1{slash}SER5-0{slash}TC4-1-Pad44)") (class "Default")
      (node (ref "U1") (pin "44") (pinfunction "PA23/SER3-1/SER5-0/TC4-1_44") (pintype "bidirectional"))
    )
    (net (code "70") (name "unconnected-(U1-PA24{slash}SER3-2{slash}SER5-2{slash}TC5-0{slash}USBDM-Pad45)") (class "Default")
      (node (ref "U1") (pin "45") (pinfunction "PA24/SER3-2/SER5-2/TC5-0/USBDM_45") (pintype "bidirectional"))
    )
    (net (code "71") (name "unconnected-(U1-PA25{slash}SER3-3{slash}SER5-3{slash}TC5-1{slash}USBDP-Pad46)") (class "Default")
      (node (ref "U1") (pin "46") (pinfunction "PA25/SER3-3/SER5-3/TC5-1/USBDP_46") (pintype "bidirectional"))
    )
    (net (code "72") (name "unconnected-(U1-PA27{slash}GCLK-1-Pad51)") (class "Default")
      (node (ref "U1") (pin "51") (pinfunction "PA27/GCLK-1_51") (pintype "bidirectional"))
    )
    (net (code "73") (name "unconnected-(U1-PB02{slash}ADC0-14{slash}SER5-0{slash}TC6-0-Pad63)") (class "Default")
      (node (ref "U1") (pin "63") (pinfunction "PB02/ADC0-14/SER5-0/TC6-0_63") (pintype "bidirectional"))
    )
    (net (code "74") (name "unconnected-(U1-PB03{slash}ADC0{slash}SER5-1{slash}TC6-Pad64)") (class "Default")
      (node (ref "U1") (pin "64") (pinfunction "PB03/ADC0/SER5-1/TC6_64") (pintype "bidirectional"))
    )
    (net (code "75") (name "unconnected-(U1-PB04{slash}ADC1-6-Pad5)") (class "Default")
      (node (ref "U1") (pin "5") (pinfunction "PB04/ADC1-6_5") (pintype "bidirectional"))
    )
    (net (code "76") (name "unconnected-(U1-PB05{slash}ADC1-7-Pad6)") (class "Default")
      (node (ref "U1") (pin "6") (pinfunction "PB05/ADC1-7_6") (pintype "bidirectional"))
    )
    (net (code "77") (name "unconnected-(U1-PB06{slash}ADC1-8-Pad9)") (class "Default")
      (node (ref "U1") (pin "9") (pinfunction "PB06/ADC1-8_9") (pintype "bidirectional"))
    )
    (net (code "78") (name "unconnected-(U1-PB07{slash}ADC1-9-Pad10)") (class "Default")
      (node (ref "U1") (pin "10") (pinfunction "PB07/ADC1-9_10") (pintype "bidirectional"))
    )
    (net (code "79") (name "unconnected-(U1-PB08{slash}ADC0-2{slash}ADC1-9{slash}SER4-0{slash}TC4-0-Pad11)") (class "Default")
      (node (ref "U1") (pin "11") (pinfunction "PB08/ADC0-2/ADC1-9/SER4-0/TC4-0_11") (pintype "bidirectional"))
    )
    (net (code "80") (name "unconnected-(U1-PB09{slash}ADC0-3{slash}ADC1-1{slash}SER4-1{slash}TC4-1-Pad12)") (class "Default")
      (node (ref "U1") (pin "12") (pinfunction "PB09/ADC0-3/ADC1-1/SER4-1/TC4-1_12") (pintype "bidirectional"))
    )
    (net (code "81") (name "unconnected-(U1-PB10{slash}SER4-2{slash}TC5-0{slash}TCC0-4-Pad23)") (class "Default")
      (node (ref "U1") (pin "23") (pinfunction "PB10/SER4-2/TC5-0/TCC0-4_23") (pintype "bidirectional"))
    )
    (net (code "82") (name "unconnected-(U1-PB11{slash}SER4-3{slash}TC5-1{slash}TCC0-5-Pad24)") (class "Default")
      (node (ref "U1") (pin "24") (pinfunction "PB11/SER4-3/TC5-1/TCC0-5_24") (pintype "bidirectional"))
    )
    (net (code "83") (name "unconnected-(U1-PB12{slash}SER4-0{slash}TC4-0-Pad25)") (class "Default")
      (node (ref "U1") (pin "25") (pinfunction "PB12/SER4-0/TC4-0_25") (pintype "bidirectional"))
    )
    (net (code "84") (name "unconnected-(U1-PB13{slash}SER4-1{slash}TC4-1-Pad26)") (class "Default")
      (node (ref "U1") (pin "26") (pinfunction "PB13/SER4-1/TC4-1_26") (pintype "bidirectional"))
    )
    (net (code "85") (name "unconnected-(U1-PB14{slash}SER4-2{slash}TC5-0-Pad27)") (class "Default")
      (node (ref "U1") (pin "27") (pinfunction "PB14/SER4-2/TC5-0_27") (pintype "bidirectional"))
    )
    (net (code "86") (name "unconnected-(U1-PB15{slash}SER4-3{slash}TC5-1-Pad28)") (class "Default")
      (node (ref "U1") (pin "28") (pinfunction "PB15/SER4-3/TC5-1_28") (pintype "bidirectional"))
    )
    (net (code "87") (name "unconnected-(U1-PB22{slash}XIN1{slash}SER1-2{slash}SER5-2{slash}TC7-0-Pad49)") (class "Default")
      (node (ref "U1") (pin "49") (pinfunction "PB22/XIN1/SER1-2/SER5-2/TC7-0_49") (pintype "bidirectional"))
    )
    (net (code "88") (name "unconnected-(U1-PB23{slash}XOUT1{slash}SER1-3{slash}SER5-3{slash}TC7-1-Pad50)") (class "Default")
      (node (ref "U1") (pin "50") (pinfunction "PB23/XOUT1/SER1-3/SER5-3/TC7-1_50") (pintype "bidirectional"))
    )
    (net (code "89") (name "unconnected-(U1-PB31{slash}SER7-1{slash}SER5-0{slash}TC0-1-Pad60)") (class "Default")
      (node (ref "U1") (pin "60") (pinfunction "PB31/SER7-1/SER5-0/TC0-1_60") (pintype "bidirectional"))
    )
    (net (code "90") (name "unconnected-(U1-VSW-Pad55)") (class "Default")
      (node (ref "U1") (pin "55") (pinfunction "VSW_55") (pintype "bidirectional"))
    )
    (net (code "91") (name "unconnected-(U2-TEST_ANA-Pad26)") (class "Default")
      (node (ref "U2") (pin "26") (pinfunction "TEST_ANA_26") (pintype "bidirectional"))
    )
  )
)
